# Arduino_and_Clock_Source.net
KiCad netlist of a schematic drawn in Altium Designer
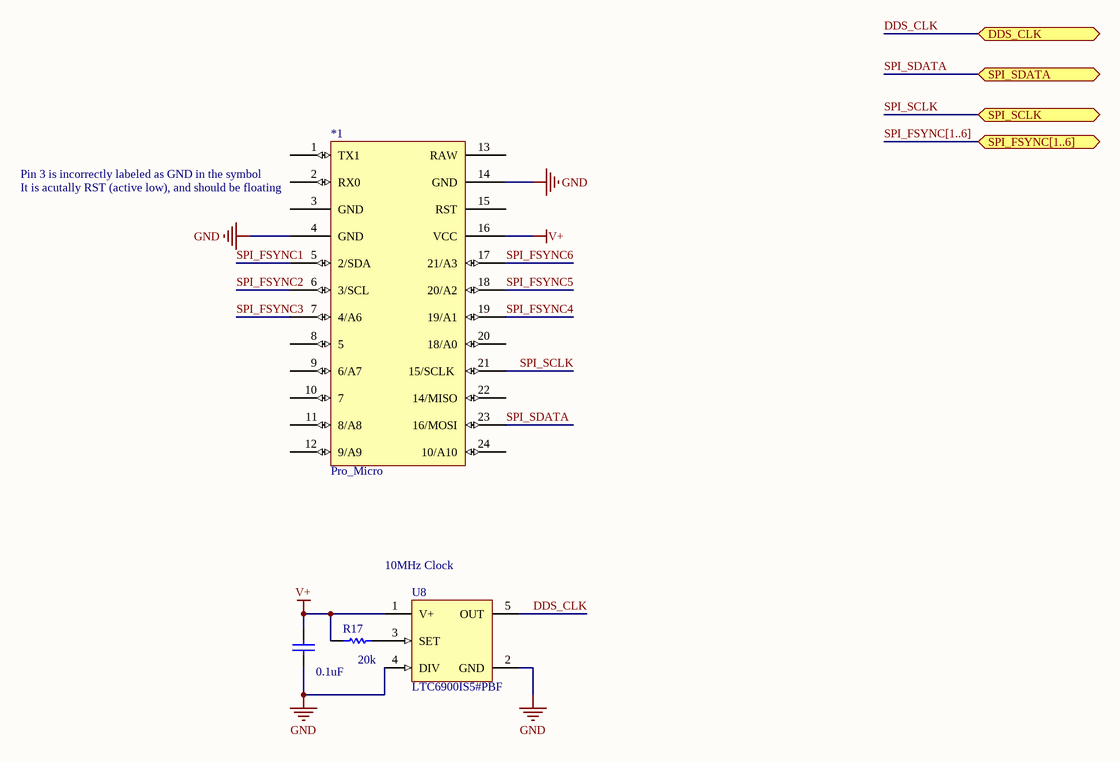
[diagram p0: Arduino_and_Clock_Source.SchDoc]

(export (version "E")
  (design (tool "Eeschema 10.0.6"))
  (components
    (comp (ref "*1")
      (value "Pro_Micro")
      (footprint "Pro_Micro")
      (libsource (lib "Pro_Micro") (part "Pro_Micro"))
    )
    (comp (ref "C22")
      (value "0.1uF")
      (footprint "1608[0603]")
      (description "Capacitor (Semiconductor SIM Model)")
      (fields (field (name "PUBLISHER") "Altium Limited"))
      (libsource (lib "Miscellaneous Devices") (part "Cap Semi"))
    )
    (comp (ref "R17")
      (value "20k")
      (footprint "6-0805_M")
      (description "Resistor")
      (fields (field (name "PUBLISHER") "Altium Limited"))
      (libsource (lib "Miscellaneous Devices") (part "Res1"))
    )
    (comp (ref "U8")
      (value "LTC6900IS5#PBF")
      (footprint "LT-TSOT-23-5_V")
      (fields (field (name "MANUFACTURER") "Linear Technology"))
      (libsource (lib "Altium Content Vault") (part "LT-LTC6900-TSOT-23-5"))
    )
  )
  (nets
    (net (code "1") (name "/DDS_CLK") (class "Default")
      (node (ref "U8") (pin "5") (pinfunction "OUT_5") (pintype "open_collector"))
    )
    (net (code "2") (name "/SPI_FSYNC1") (class "Default")
      (node (ref "*1") (pin "5") (pinfunction "2/SDA_5") (pintype "bidirectional"))
    )
    (net (code "3") (name "/SPI_FSYNC2") (class "Default")
      (node (ref "*1") (pin "6") (pinfunction "3/SCL_6") (pintype "bidirectional"))
    )
    (net (code "4") (name "/SPI_FSYNC3") (class "Default")
      (node (ref "*1") (pin "7") (pinfunction "4/A6_7") (pintype "bidirectional"))
    )
    (net (code "5") (name "/SPI_FSYNC4") (class "Default")
      (node (ref "*1") (pin "19") (pinfunction "19/A1_19") (pintype "bidirectional"))
    )
    (net (code "6") (name "/SPI_FSYNC5") (class "Default")
      (node (ref "*1") (pin "18") (pinfunction "20/A2_18") (pintype "bidirectional"))
    )
    (net (code "7") (name "/SPI_FSYNC6") (class "Default")
      (node (ref "*1") (pin "17") (pinfunction "21/A3_17") (pintype "bidirectional"))
    )
    (net (code "9") (name "/SPI_SCLK") (class "Default")
      (node (ref "*1") (pin "21") (pinfunction "15/SCLK_21") (pintype "bidirectional"))
    )
    (net (code "10") (name "/SPI_SDATA") (class "Default")
      (node (ref "*1") (pin "23") (pinfunction "16/MOSI_23") (pintype "bidirectional"))
    )
    (net (code "11") (name "GND") (class "Default")
      (node (ref "*1") (pin "14") (pinfunction "GND_14") (pintype "passive"))
      (node (ref "*1") (pin "4") (pinfunction "GND_4") (pintype "passive"))
      (node (ref "C22") (pin "1") (pinfunction "1_1") (pintype "passive"))
      (node (ref "U8") (pin "2") (pinfunction "GND_2") (pintype "power_in"))
      (node (ref "U8") (pin "4") (pinfunction "DIV_4") (pintype "input"))
    )
    (net (code "12") (name "Net-(U8-SET)") (class "Default")
      (node (ref "R17") (pin "2") (pinfunction "2_2") (pintype "passive"))
      (node (ref "U8") (pin "3") (pinfunction "SET_3") (pintype "input"))
    )
    (net (code "13") (name "V+") (class "Default")
      (node (ref "*1") (pin "16") (pinfunction "VCC_16") (pintype "passive"))
      (node (ref "C22") (pin "2") (pinfunction "2_2") (pintype "passive"))
      (node (ref "R17") (pin "1") (pinfunction "1_1") (pintype "passive"))
      (node (ref "U8") (pin "1") (pinfunction "V+_1") (pintype "power_in"))
    )
    (net (code "14") (name "unconnected-(*1-5-Pad8)") (class "Default")
      (node (ref "*1") (pin "8") (pinfunction "5_8") (pintype "bidirectional"))
    )
    (net (code "15") (name "unconnected-(*1-6{slash}A7-Pad9)") (class "Default")
      (node (ref "*1") (pin "9") (pinfunction "6/A7_9") (pintype "bidirectional"))
    )
    (net (code "16") (name "unconnected-(*1-7-Pad10)") (class "Default")
      (node (ref "*1") (pin "10") (pinfunction "7_10") (pintype "bidirectional"))
    )
    (net (code "17") (name "unconnected-(*1-8{slash}A8-Pad11)") (class "Default")
      (node (ref "*1") (pin "11") (pinfunction "8/A8_11") (pintype "bidirectional"))
    )
    (net (code "18") (name "unconnected-(*1-9{slash}A9-Pad12)") (class "Default")
      (node (ref "*1") (pin "12") (pinfunction "9/A9_12") (pintype "bidirectional"))
    )
    (net (code "19") (name "unconnected-(*1-10{slash}A10-Pad24)") (class "Default")
      (node (ref "*1") (pin "24") (pinfunction "10/A10_24") (pintype "bidirectional"))
    )
    (net (code "20") (name "unconnected-(*1-14{slash}MISO-Pad22)") (class "Default")
      (node (ref "*1") (pin "22") (pinfunction "14/MISO_22") (pintype "bidirectional"))
    )
    (net (code "21") (name "unconnected-(*1-18{slash}A0-Pad20)") (class "Default")
      (node (ref "*1") (pin "20") (pinfunction "18/A0_20") (pintype "bidirectional"))
    )
    (net (code "22") (name "unconnected-(*1-GND-Pad3)") (class "Default")
      (node (ref "*1") (pin "3") (pinfunction "GND_3") (pintype "passive"))
    )
    (net (code "23") (name "unconnected-(*1-RAW-Pad13)") (class "Default")
      (node (ref "*1") (pin "13") (pinfunction "RAW_13") (pintype "passive"))
    )
    (net (code "24") (name "unconnected-(*1-RST-Pad15)") (class "Default")
      (node (ref "*1") (pin "15") (pinfunction "RST_15") (pintype "passive"))
    )
    (net (code "25") (name "unconnected-(*1-RX0-Pad2)") (class "Default")
      (node (ref "*1") (pin "2") (pinfunction "RX0_2") (pintype "bidirectional"))
    )
    (net (code "26") (name "unconnected-(*1-TX1-Pad1)") (class "Default")
      (node (ref "*1") (pin "1") (pinfunction "TX1_1") (pintype "bidirectional"))
    )
  )
)
